# Adafruit_EZ-Link_Breakout.net
KiCad netlist of a schematic drawn in EAGLE
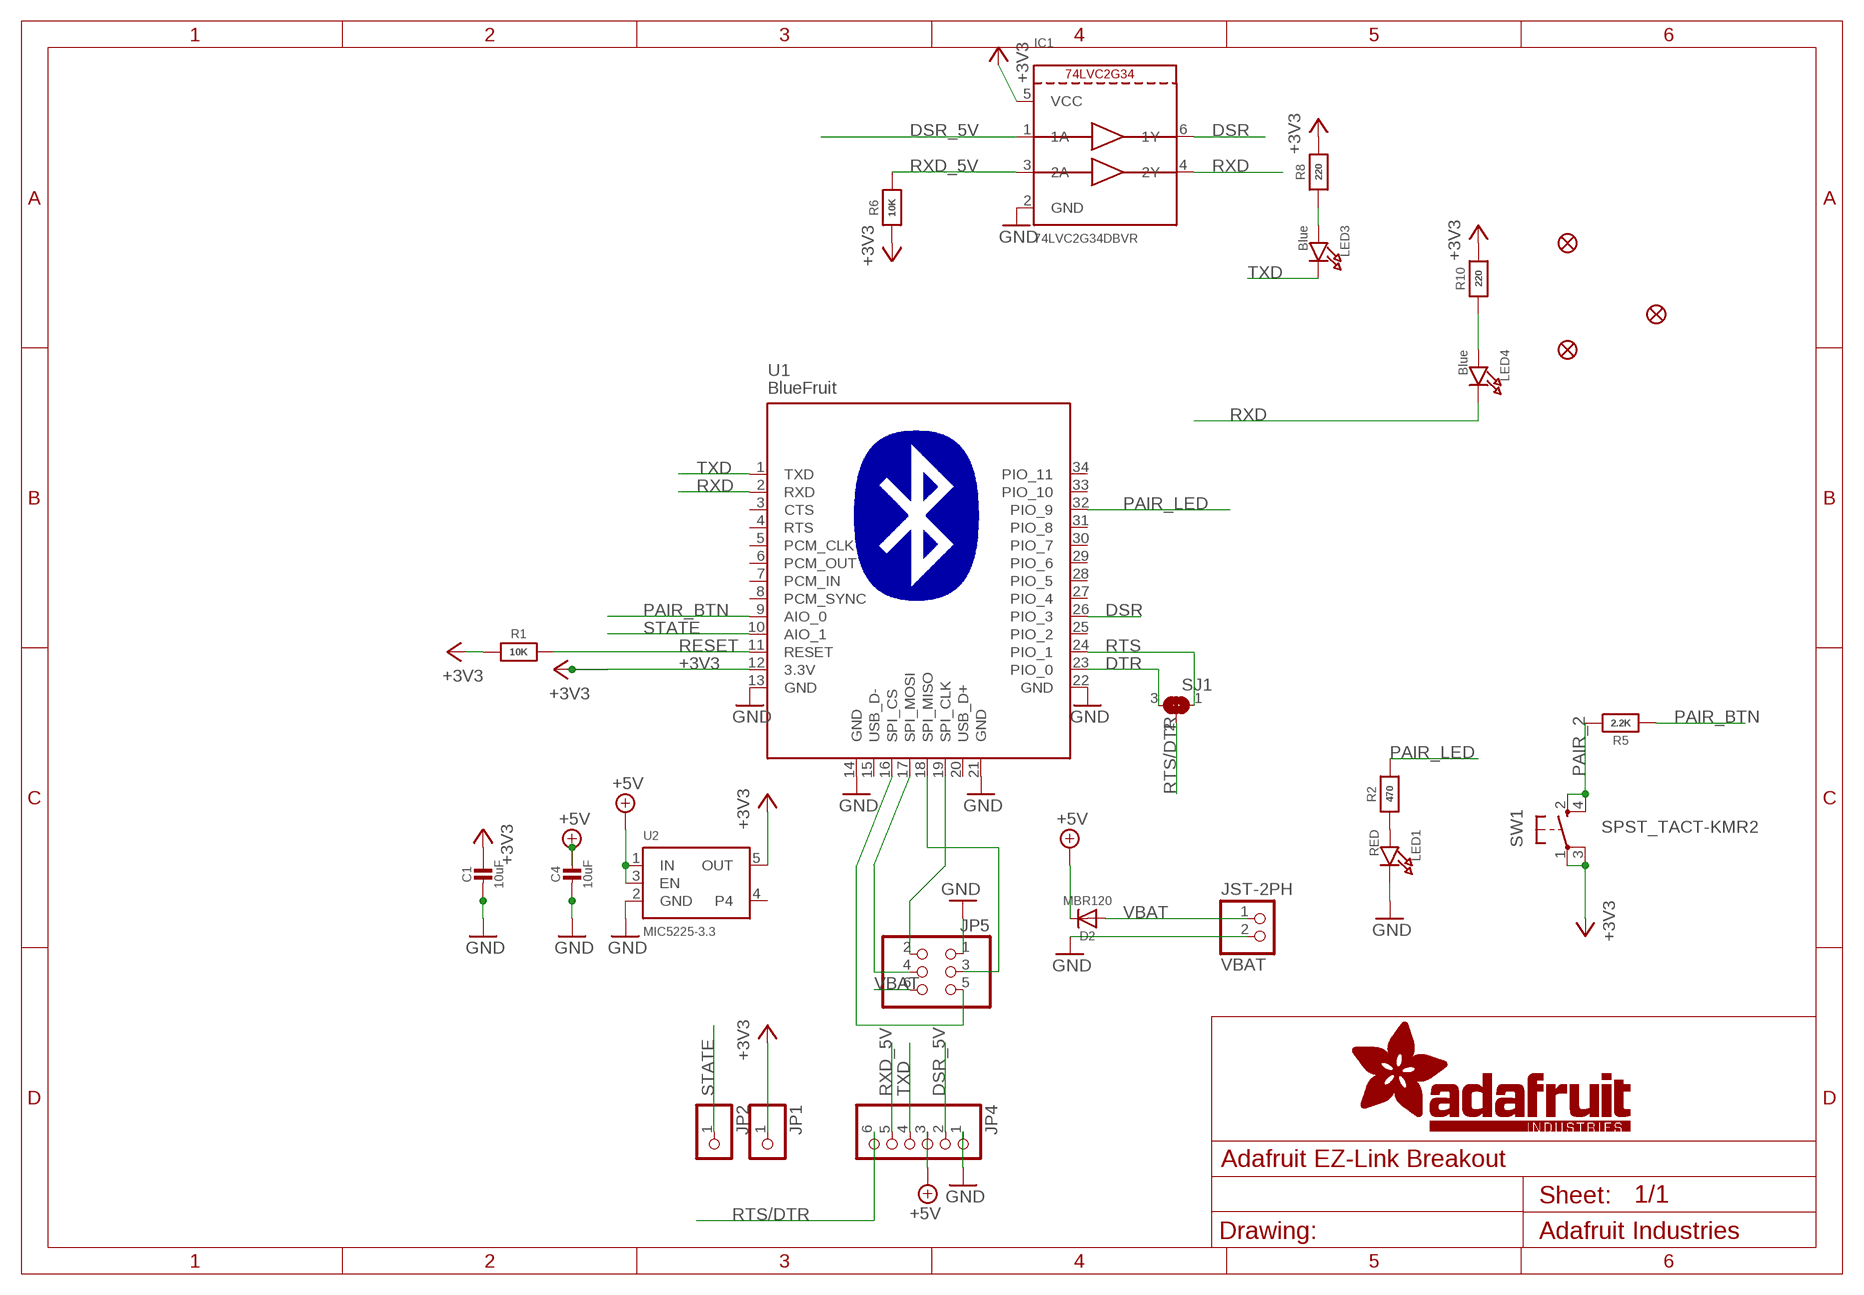
[diagram p0: schematic, sheet 1]

(export (version "E")
  (design (tool "Eeschema 10.0.6"))
  (components
    (comp (ref "C1")
      (value "10uF")
      (footprint "eagle-import:0805-NO")
      (libsource (lib "eagle-import") (part "CAP_CERAMIC0805-NOOUTLINE"))
    )
    (comp (ref "C4")
      (value "10uF")
      (footprint "eagle-import:0805-NO")
      (libsource (lib "eagle-import") (part "CAP_CERAMIC0805-NOOUTLINE"))
    )
    (comp (ref "D2")
      (value "MBR120")
      (footprint "eagle-import:SOD-123")
      (libsource (lib "eagle-import") (part "DIODESOD-123"))
    )
    (comp (ref "FID1")
      (value "FIDUCIAL\"\"")
      (footprint "eagle-import:FIDUCIAL_1MM")
      (libsource (lib "eagle-import") (part "FIDUCIAL{dblquote}{dblquote}"))
    )
    (comp (ref "FID2")
      (value "FIDUCIAL\"\"")
      (footprint "eagle-import:FIDUCIAL_1MM")
      (libsource (lib "eagle-import") (part "FIDUCIAL{dblquote}{dblquote}"))
    )
    (comp (ref "FID3")
      (value "FIDUCIAL\"\"")
      (footprint "eagle-import:FIDUCIAL_1MM")
      (libsource (lib "eagle-import") (part "FIDUCIAL{dblquote}{dblquote}"))
    )
    (comp (ref "IC1")
      (value "74LVC2G34DBVR")
      (footprint "eagle-import:SOT23-6")
      (libsource (lib "eagle-import") (part "74LVC2G34DBVR"))
    )
    (comp (ref "JP1")
      (value "PINHD-1X1CB")
      (footprint "eagle-import:1X01-CLEANBIG")
      (libsource (lib "eagle-import") (part "PINHD-1X1CB"))
    )
    (comp (ref "JP2")
      (value "PINHD-1X1CB")
      (footprint "eagle-import:1X01-CLEANBIG")
      (libsource (lib "eagle-import") (part "PINHD-1X1CB"))
    )
    (comp (ref "JP4")
      (value "PINHD-1X6B")
      (footprint "eagle-import:1X06-BIG")
      (libsource (lib "eagle-import") (part "PINHD-1X6B"))
    )
    (comp (ref "JP5")
      (value "HEADER-2X3")
      (footprint "eagle-import:2X03_ROUND_70MIL")
      (libsource (lib "eagle-import") (part "HEADER-2X3"))
    )
    (comp (ref "LED1")
      (value "RED")
      (footprint "eagle-import:CHIPLED_0805_NOOUTLINE")
      (libsource (lib "eagle-import") (part "LED0805_NOOUTLINE"))
    )
    (comp (ref "LED3")
      (value "Blue")
      (footprint "eagle-import:CHIPLED_0805_NOOUTLINE")
      (libsource (lib "eagle-import") (part "LED0805_NOOUTLINE"))
    )
    (comp (ref "LED4")
      (value "Blue")
      (footprint "eagle-import:CHIPLED_0805_NOOUTLINE")
      (libsource (lib "eagle-import") (part "LED0805_NOOUTLINE"))
    )
    (comp (ref "R1")
      (value "10K")
      (footprint "eagle-import:0805-NO")
      (libsource (lib "eagle-import") (part "RESISTOR0805_NOOUTLINE"))
    )
    (comp (ref "R2")
      (value "470")
      (footprint "eagle-import:0805-NO")
      (libsource (lib "eagle-import") (part "RESISTOR0805_NOOUTLINE"))
    )
    (comp (ref "R5")
      (value "2.2K")
      (footprint "eagle-import:0805-NO")
      (libsource (lib "eagle-import") (part "RESISTOR0805_NOOUTLINE"))
    )
    (comp (ref "R6")
      (value "10K")
      (footprint "eagle-import:_0805MP")
      (libsource (lib "eagle-import") (part "RESISTOR_0805MP"))
    )
    (comp (ref "R8")
      (value "220")
      (footprint "eagle-import:0805-NO")
      (libsource (lib "eagle-import") (part "RESISTOR0805_NOOUTLINE"))
    )
    (comp (ref "R10")
      (value "220")
      (footprint "eagle-import:0805-NO")
      (libsource (lib "eagle-import") (part "RESISTOR0805_NOOUTLINE"))
    )
    (comp (ref "SJ1")
      (value "SOLDERJUMPER_2WAY")
      (footprint "eagle-import:SOLDERJUMPER_2WAY_OPEN_NOPASTE")
      (libsource (lib "eagle-import") (part "SOLDERJUMPER_2WAY"))
    )
    (comp (ref "SW1")
      (value "SPST_TACT-KMR2")
      (footprint "eagle-import:KMR2")
      (libsource (lib "eagle-import") (part "SPST_TACT-KMR2"))
    )
    (comp (ref "U1")
      (value "BlueFruit")
      (footprint "eagle-import:BLUETOOTH_MODULE")
      (libsource (lib "eagle-import") (part "BLUETOOTH_MODULE"))
    )
    (comp (ref "U2")
      (value "MIC5225-3.3")
      (footprint "eagle-import:SOT23-5")
      (libsource (lib "eagle-import") (part "VREG_SOT23-5"))
    )
    (comp (ref "VBAT")
      (value "JST-2PH")
      (footprint "eagle-import:JST-PH-2-SMT-RA")
      (libsource (lib "eagle-import") (part "JST_2PIN-SMT-RA"))
    )
  )
  (nets
    (net (code "1") (name "+3V3") (class "Default")
      (node (ref "C1") (pin "1") (pinfunction "1_1") (pintype "passive"))
      (node (ref "IC1") (pin "5") (pinfunction "VCC_5") (pintype "power_in"))
      (node (ref "JP1") (pin "1") (pinfunction "1_1") (pintype "passive"))
      (node (ref "R1") (pin "1") (pinfunction "1_1") (pintype "passive"))
      (node (ref "R10") (pin "2") (pinfunction "2_2") (pintype "passive"))
      (node (ref "R6") (pin "1") (pinfunction "1_1") (pintype "passive"))
      (node (ref "R8") (pin "2") (pinfunction "2_2") (pintype "passive"))
      (node (ref "SW1") (pin "1") (pinfunction "P_1") (pintype "passive"))
      (node (ref "SW1") (pin "3") (pinfunction "P1_3") (pintype "passive"))
      (node (ref "U1") (pin "12") (pinfunction "3.3V_12") (pintype "power_in"))
      (node (ref "U2") (pin "5") (pinfunction "OUT_5") (pintype "power_in"))
    )
    (net (code "2") (name "+5V") (class "Default")
      (node (ref "C4") (pin "1") (pinfunction "1_1") (pintype "passive"))
      (node (ref "D2") (pin "C") (pinfunction "C_C") (pintype "passive"))
      (node (ref "JP4") (pin "3") (pinfunction "3_3") (pintype "passive"))
      (node (ref "U2") (pin "1") (pinfunction "IN_1") (pintype "power_in"))
      (node (ref "U2") (pin "3") (pinfunction "EN_3") (pintype "input"))
    )
    (net (code "3") (name "/DSR") (class "Default")
      (node (ref "IC1") (pin "6") (pinfunction "1Y_6") (pintype "output"))
      (node (ref "U1") (pin "26") (pinfunction "PIO_3_26") (pintype "bidirectional"))
    )
    (net (code "4") (name "/DSR_5V") (class "Default")
      (node (ref "IC1") (pin "1") (pinfunction "1A_1") (pintype "input"))
      (node (ref "JP4") (pin "2") (pinfunction "2_2") (pintype "passive"))
    )
    (net (code "5") (name "/DTR") (class "Default")
      (node (ref "SJ1") (pin "3") (pinfunction "3_3") (pintype "passive"))
      (node (ref "U1") (pin "23") (pinfunction "PIO_0_23") (pintype "bidirectional"))
    )
    (net (code "6") (name "/PAIR_2") (class "Default")
      (node (ref "R5") (pin "2") (pinfunction "2_2") (pintype "passive"))
      (node (ref "SW1") (pin "2") (pinfunction "S_2") (pintype "passive"))
      (node (ref "SW1") (pin "4") (pinfunction "S1_4") (pintype "passive"))
    )
    (net (code "7") (name "/PAIR_BTN") (class "Default")
      (node (ref "R5") (pin "1") (pinfunction "1_1") (pintype "passive"))
      (node (ref "U1") (pin "9") (pinfunction "AIO_0_9") (pintype "bidirectional"))
    )
    (net (code "8") (name "/PAIR_LED") (class "Default")
      (node (ref "R2") (pin "2") (pinfunction "2_2") (pintype "passive"))
      (node (ref "U1") (pin "32") (pinfunction "PIO_9_32") (pintype "bidirectional"))
    )
    (net (code "9") (name "/RESET") (class "Default")
      (node (ref "R1") (pin "2") (pinfunction "2_2") (pintype "passive"))
      (node (ref "U1") (pin "11") (pinfunction "RESET_11") (pintype "bidirectional"))
    )
    (net (code "10") (name "/RTS") (class "Default")
      (node (ref "SJ1") (pin "1") (pinfunction "1_1") (pintype "passive"))
      (node (ref "U1") (pin "24") (pinfunction "PIO_1_24") (pintype "bidirectional"))
    )
    (net (code "11") (name "/RTS{slash}DTR") (class "Default")
      (node (ref "JP4") (pin "6") (pinfunction "6_6") (pintype "passive"))
      (node (ref "SJ1") (pin "2") (pinfunction "2_2") (pintype "passive"))
    )
    (net (code "12") (name "/RXD") (class "Default")
      (node (ref "IC1") (pin "4") (pinfunction "2Y_4") (pintype "output"))
      (node (ref "LED4") (pin "C") (pinfunction "C_C") (pintype "passive"))
      (node (ref "U1") (pin "2") (pinfunction "RXD_2") (pintype "bidirectional"))
    )
    (net (code "13") (name "/RXD_5V") (class "Default")
      (node (ref "IC1") (pin "3") (pinfunction "2A_3") (pintype "input"))
      (node (ref "JP4") (pin "5") (pinfunction "5_5") (pintype "passive"))
      (node (ref "R6") (pin "2") (pinfunction "2_2") (pintype "passive"))
    )
    (net (code "14") (name "/STATE") (class "Default")
      (node (ref "JP2") (pin "1") (pinfunction "1_1") (pintype "passive"))
      (node (ref "U1") (pin "10") (pinfunction "AIO_1_10") (pintype "bidirectional"))
    )
    (net (code "15") (name "/TXD") (class "Default")
      (node (ref "JP4") (pin "4") (pinfunction "4_4") (pintype "passive"))
      (node (ref "LED3") (pin "C") (pinfunction "C_C") (pintype "passive"))
      (node (ref "U1") (pin "1") (pinfunction "TXD_1") (pintype "bidirectional"))
    )
    (net (code "16") (name "/VBAT") (class "Default")
      (node (ref "D2") (pin "A") (pinfunction "A_A") (pintype "passive"))
      (node (ref "JP5") (pin "6") (pinfunction "6_6") (pintype "passive"))
      (node (ref "VBAT") (pin "1") (pinfunction "2_1") (pintype "passive"))
    )
    (net (code "17") (name "GND") (class "Default")
      (node (ref "C1") (pin "2") (pinfunction "2_2") (pintype "passive"))
      (node (ref "C4") (pin "2") (pinfunction "2_2") (pintype "passive"))
      (node (ref "IC1") (pin "2") (pinfunction "GND_2") (pintype "power_in"))
      (node (ref "JP4") (pin "1") (pinfunction "1_1") (pintype "passive"))
      (node (ref "JP5") (pin "1") (pinfunction "1_1") (pintype "passive"))
      (node (ref "LED1") (pin "C") (pinfunction "C_C") (pintype "passive"))
      (node (ref "U1") (pin "13") (pinfunction "GND_13") (pintype "power_in"))
      (node (ref "U1") (pin "14") (pinfunction "GND_14") (pintype "power_in"))
      (node (ref "U1") (pin "21") (pinfunction "GND_21") (pintype "power_in"))
      (node (ref "U1") (pin "22") (pinfunction "GND_22") (pintype "power_in"))
      (node (ref "U2") (pin "2") (pinfunction "GND_2") (pintype "power_in"))
      (node (ref "VBAT") (pin "2") (pinfunction "1_2") (pintype "passive"))
    )
    (net (code "18") (name "Net-(LED1-PadA)") (class "Default")
      (node (ref "LED1") (pin "A") (pinfunction "A_A") (pintype "passive"))
      (node (ref "R2") (pin "1") (pinfunction "1_1") (pintype "passive"))
    )
    (net (code "19") (name "Net-(LED3-PadA)") (class "Default")
      (node (ref "LED3") (pin "A") (pinfunction "A_A") (pintype "passive"))
      (node (ref "R8") (pin "1") (pinfunction "1_1") (pintype "passive"))
    )
    (net (code "20") (name "Net-(LED4-PadA)") (class "Default")
      (node (ref "LED4") (pin "A") (pinfunction "A_A") (pintype "passive"))
      (node (ref "R10") (pin "1") (pinfunction "1_1") (pintype "passive"))
    )
    (net (code "21") (name "Net-(U1-SPI_CLK)") (class "Default")
      (node (ref "JP5") (pin "2") (pinfunction "2_2") (pintype "passive"))
      (node (ref "U1") (pin "19") (pinfunction "SPI_CLK_19") (pintype "bidirectional"))
    )
    (net (code "22") (name "Net-(U1-SPI_CS)") (class "Default")
      (node (ref "JP5") (pin "5") (pinfunction "5_5") (pintype "passive"))
      (node (ref "U1") (pin "16") (pinfunction "SPI_CS_16") (pintype "bidirectional"))
    )
    (net (code "23") (name "Net-(U1-SPI_MISO)") (class "Default")
      (node (ref "JP5") (pin "3") (pinfunction "3_3") (pintype "passive"))
      (node (ref "U1") (pin "18") (pinfunction "SPI_MISO_18") (pintype "bidirectional"))
    )
    (net (code "24") (name "Net-(U1-SPI_MOSI)") (class "Default")
      (node (ref "JP5") (pin "4") (pinfunction "4_4") (pintype "passive"))
      (node (ref "U1") (pin "17") (pinfunction "SPI_MOSI_17") (pintype "bidirectional"))
    )
    (net (code "25") (name "unconnected-(U1-CTS-Pad3)") (class "Default")
      (node (ref "U1") (pin "3") (pinfunction "CTS_3") (pintype "bidirectional"))
    )
    (net (code "26") (name "unconnected-(U1-PCM_CLK-Pad5)") (class "Default")
      (node (ref "U1") (pin "5") (pinfunction "PCM_CLK_5") (pintype "bidirectional"))
    )
    (net (code "27") (name "unconnected-(U1-PCM_IN-Pad7)") (class "Default")
      (node (ref "U1") (pin "7") (pinfunction "PCM_IN_7") (pintype "bidirectional"))
    )
    (net (code "28") (name "unconnected-(U1-PCM_OUT-Pad6)") (class "Default")
      (node (ref "U1") (pin "6") (pinfunction "PCM_OUT_6") (pintype "bidirectional"))
    )
    (net (code "29") (name "unconnected-(U1-PCM_SYNC-Pad8)") (class "Default")
      (node (ref "U1") (pin "8") (pinfunction "PCM_SYNC_8") (pintype "bidirectional"))
    )
    (net (code "30") (name "unconnected-(U1-PIO_2-Pad25)") (class "Default")
      (node (ref "U1") (pin "25") (pinfunction "PIO_2_25") (pintype "bidirectional"))
    )
    (net (code "31") (name "unconnected-(U1-PIO_4-Pad27)") (class "Default")
      (node (ref "U1") (pin "27") (pinfunction "PIO_4_27") (pintype "bidirectional"))
    )
    (net (code "32") (name "unconnected-(U1-PIO_5-Pad28)") (class "Default")
      (node (ref "U1") (pin "28") (pinfunction "PIO_5_28") (pintype "bidirectional"))
    )
    (net (code "33") (name "unconnected-(U1-PIO_6-Pad29)") (class "Default")
      (node (ref "U1") (pin "29") (pinfunction "PIO_6_29") (pintype "bidirectional"))
    )
    (net (code "34") (name "unconnected-(U1-PIO_7-Pad30)") (class "Default")
      (node (ref "U1") (pin "30") (pinfunction "PIO_7_30") (pintype "bidirectional"))
    )
    (net (code "35") (name "unconnected-(U1-PIO_8-Pad31)") (class "Default")
      (node (ref "U1") (pin "31") (pinfunction "PIO_8_31") (pintype "bidirectional"))
    )
    (net (code "36") (name "unconnected-(U1-PIO_10-Pad33)") (class "Default")
      (node (ref "U1") (pin "33") (pinfunction "PIO_10_33") (pintype "bidirectional"))
    )
    (net (code "37") (name "unconnected-(U1-PIO_11-Pad34)") (class "Default")
      (node (ref "U1") (pin "34") (pinfunction "PIO_11_34") (pintype "bidirectional"))
    )
    (net (code "38") (name "unconnected-(U1-RTS-Pad4)") (class "Default")
      (node (ref "U1") (pin "4") (pinfunction "RTS_4") (pintype "bidirectional"))
    )
    (net (code "39") (name "unconnected-(U1-USB_D+-Pad20)") (class "Default")
      (node (ref "U1") (pin "20") (pinfunction "USB_D+_20") (pintype "bidirectional"))
    )
    (net (code "40") (name "unconnected-(U1-USB_D--Pad15)") (class "Default")
      (node (ref "U1") (pin "15") (pinfunction "USB_D-_15") (pintype "bidirectional"))
    )
    (net (code "41") (name "unconnected-(U2-P4-Pad4)") (class "Default")
      (node (ref "U2") (pin "4") (pinfunction "P4_4") (pintype "bidirectional"))
    )
  )
)
